# PowerSupply.net
KiCad netlist of a schematic drawn in Altium Designer
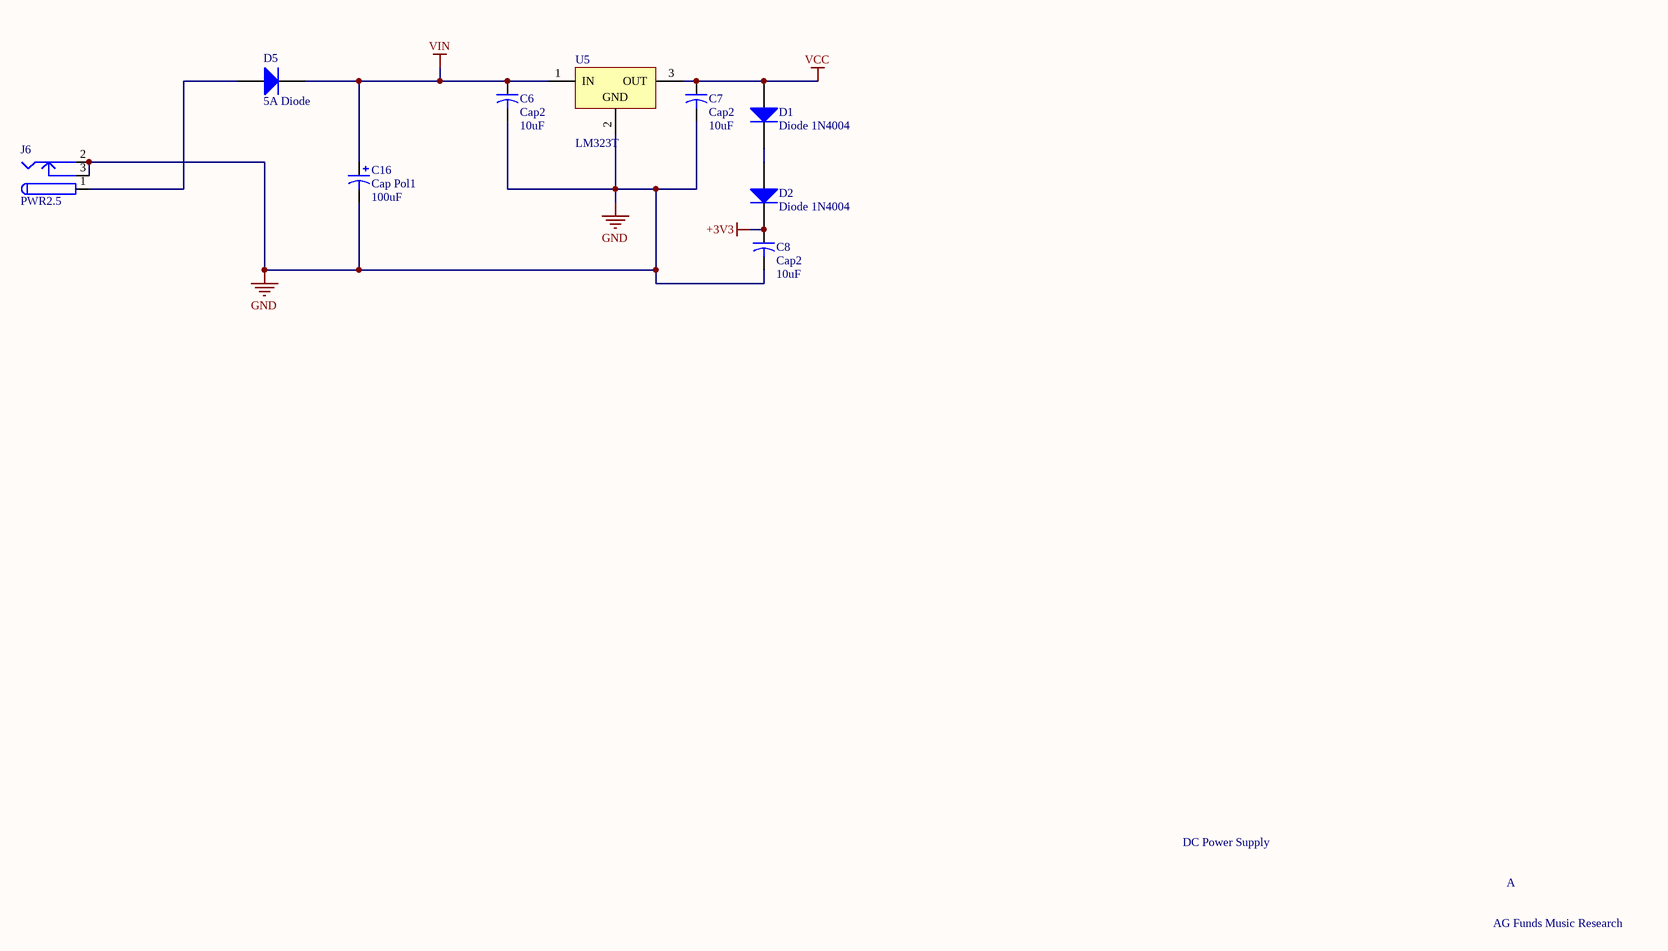
[diagram p0: PowerSupply.SchDoc]

(export (version "E")
  (design (tool "Eeschema 10.0.6"))
  (components
    (comp (ref "C6")
      (value "Cap2")
      (footprint "CAPR5-4X5")
      (description "Capacitor")
      (fields (field (name "ALTIUM_VALUE") "10uF") (field (name "PUBLISHER") "Altium Limited"))
      (libsource (lib "Miscellaneous Devices") (part "Cap2"))
    )
    (comp (ref "C7")
      (value "Cap2")
      (footprint "CAPR5-4X5")
      (description "Capacitor")
      (fields (field (name "ALTIUM_VALUE") "10uF") (field (name "PUBLISHER") "Altium Limited"))
      (libsource (lib "Miscellaneous Devices") (part "Cap2"))
    )
    (comp (ref "C8")
      (value "Cap2")
      (footprint "CAPR5-4X5")
      (description "Capacitor")
      (fields (field (name "ALTIUM_VALUE") "10uF") (field (name "PUBLISHER") "Altium Limited"))
      (libsource (lib "Miscellaneous Devices") (part "Cap2"))
    )
    (comp (ref "C16")
      (value "Cap Pol1")
      (footprint "RB7.6-15")
      (description "Polarized Capacitor (Radial)")
      (fields (field (name "ALTIUM_VALUE") "100uF") (field (name "PUBLISHER") "Altium Limited"))
      (libsource (lib "Miscellaneous Devices") (part "Cap Pol1"))
    )
    (comp (ref "D1")
      (value "Diode 1N4004")
      (footprint "DO-41")
      (description "1 Amp General Purpose Rectifier")
      (fields (field (name "PUBLISHER") "Altium Limited"))
      (libsource (lib "Miscellaneous Devices") (part "Diode 1N4004"))
    )
    (comp (ref "D2")
      (value "Diode 1N4004")
      (footprint "DO-41")
      (description "1 Amp General Purpose Rectifier")
      (fields (field (name "PUBLISHER") "Altium Limited"))
      (libsource (lib "Miscellaneous Devices") (part "Diode 1N4004"))
    )
    (comp (ref "D5")
      (value "5A Diode")
      (footprint "DO-201AD")
      (description "3 Amp General Purpose Rectifier")
      (fields (field (name "PUBLISHER") "Altium Limited"))
      (libsource (lib "Miscellaneous Devices") (part "Diode 1N5404"))
    )
    (comp (ref "J6")
      (value "PWR2.5")
      (footprint "PJ-102B")
      (description "CUI Inc. PJ-102B Low Voltage Power Supply Connector")
      (fields (field (name "PUBLISHER") "Altium Limited"))
      (libsource (lib "MIDIPiano_7") (part "PWR2.5"))
    )
    (comp (ref "U5")
      (value "LM323T")
      (footprint "TO220ABN")
      (description "Three Terminal 3A-5V Positive Voltage Regulator")
      (fields (field (name "PUBLISHER") "Altium Limited"))
      (libsource (lib "ST Power Mgt Voltage Regulator") (part "LM323T"))
    )
  )
  (nets
    (net (code "1") (name "+3V3") (class "Default")
      (node (ref "C8") (pin "1") (pinfunction "1_1") (pintype "passive"))
      (node (ref "D2") (pin "2") (pinfunction "K_2") (pintype "passive"))
    )
    (net (code "2") (name "GND") (class "Default")
      (node (ref "C16") (pin "2") (pinfunction "2_2") (pintype "passive"))
      (node (ref "C6") (pin "2") (pinfunction "2_2") (pintype "passive"))
      (node (ref "C7") (pin "2") (pinfunction "2_2") (pintype "passive"))
      (node (ref "C8") (pin "2") (pinfunction "2_2") (pintype "passive"))
      (node (ref "J6") (pin "2") (pinfunction "2_2") (pintype "power_in"))
      (node (ref "J6") (pin "3") (pinfunction "3_3") (pintype "power_in"))
      (node (ref "U5") (pin "2") (pinfunction "GND_2") (pintype "power_in"))
    )
    (net (code "3") (name "Net-(D1-K)") (class "Default")
      (node (ref "D1") (pin "2") (pinfunction "K_2") (pintype "passive"))
      (node (ref "D2") (pin "1") (pinfunction "A_1") (pintype "passive"))
    )
    (net (code "4") (name "Net-(D5-A)") (class "Default")
      (node (ref "D5") (pin "1") (pinfunction "A_1") (pintype "passive"))
      (node (ref "J6") (pin "1") (pinfunction "1_1") (pintype "power_in"))
    )
    (net (code "5") (name "VCC") (class "Default")
      (node (ref "C7") (pin "1") (pinfunction "1_1") (pintype "passive"))
      (node (ref "D1") (pin "1") (pinfunction "A_1") (pintype "passive"))
      (node (ref "U5") (pin "3") (pinfunction "OUT_3") (pintype "power_in"))
    )
    (net (code "6") (name "VIN") (class "Default")
      (node (ref "C16") (pin "1") (pinfunction "1_1") (pintype "passive"))
      (node (ref "C6") (pin "1") (pinfunction "1_1") (pintype "passive"))
      (node (ref "D5") (pin "2") (pinfunction "K_2") (pintype "passive"))
      (node (ref "U5") (pin "1") (pinfunction "IN_1") (pintype "power_in"))
    )
  )
)
